# 21318.net
KiCad netlist of a schematic drawn in EAGLE
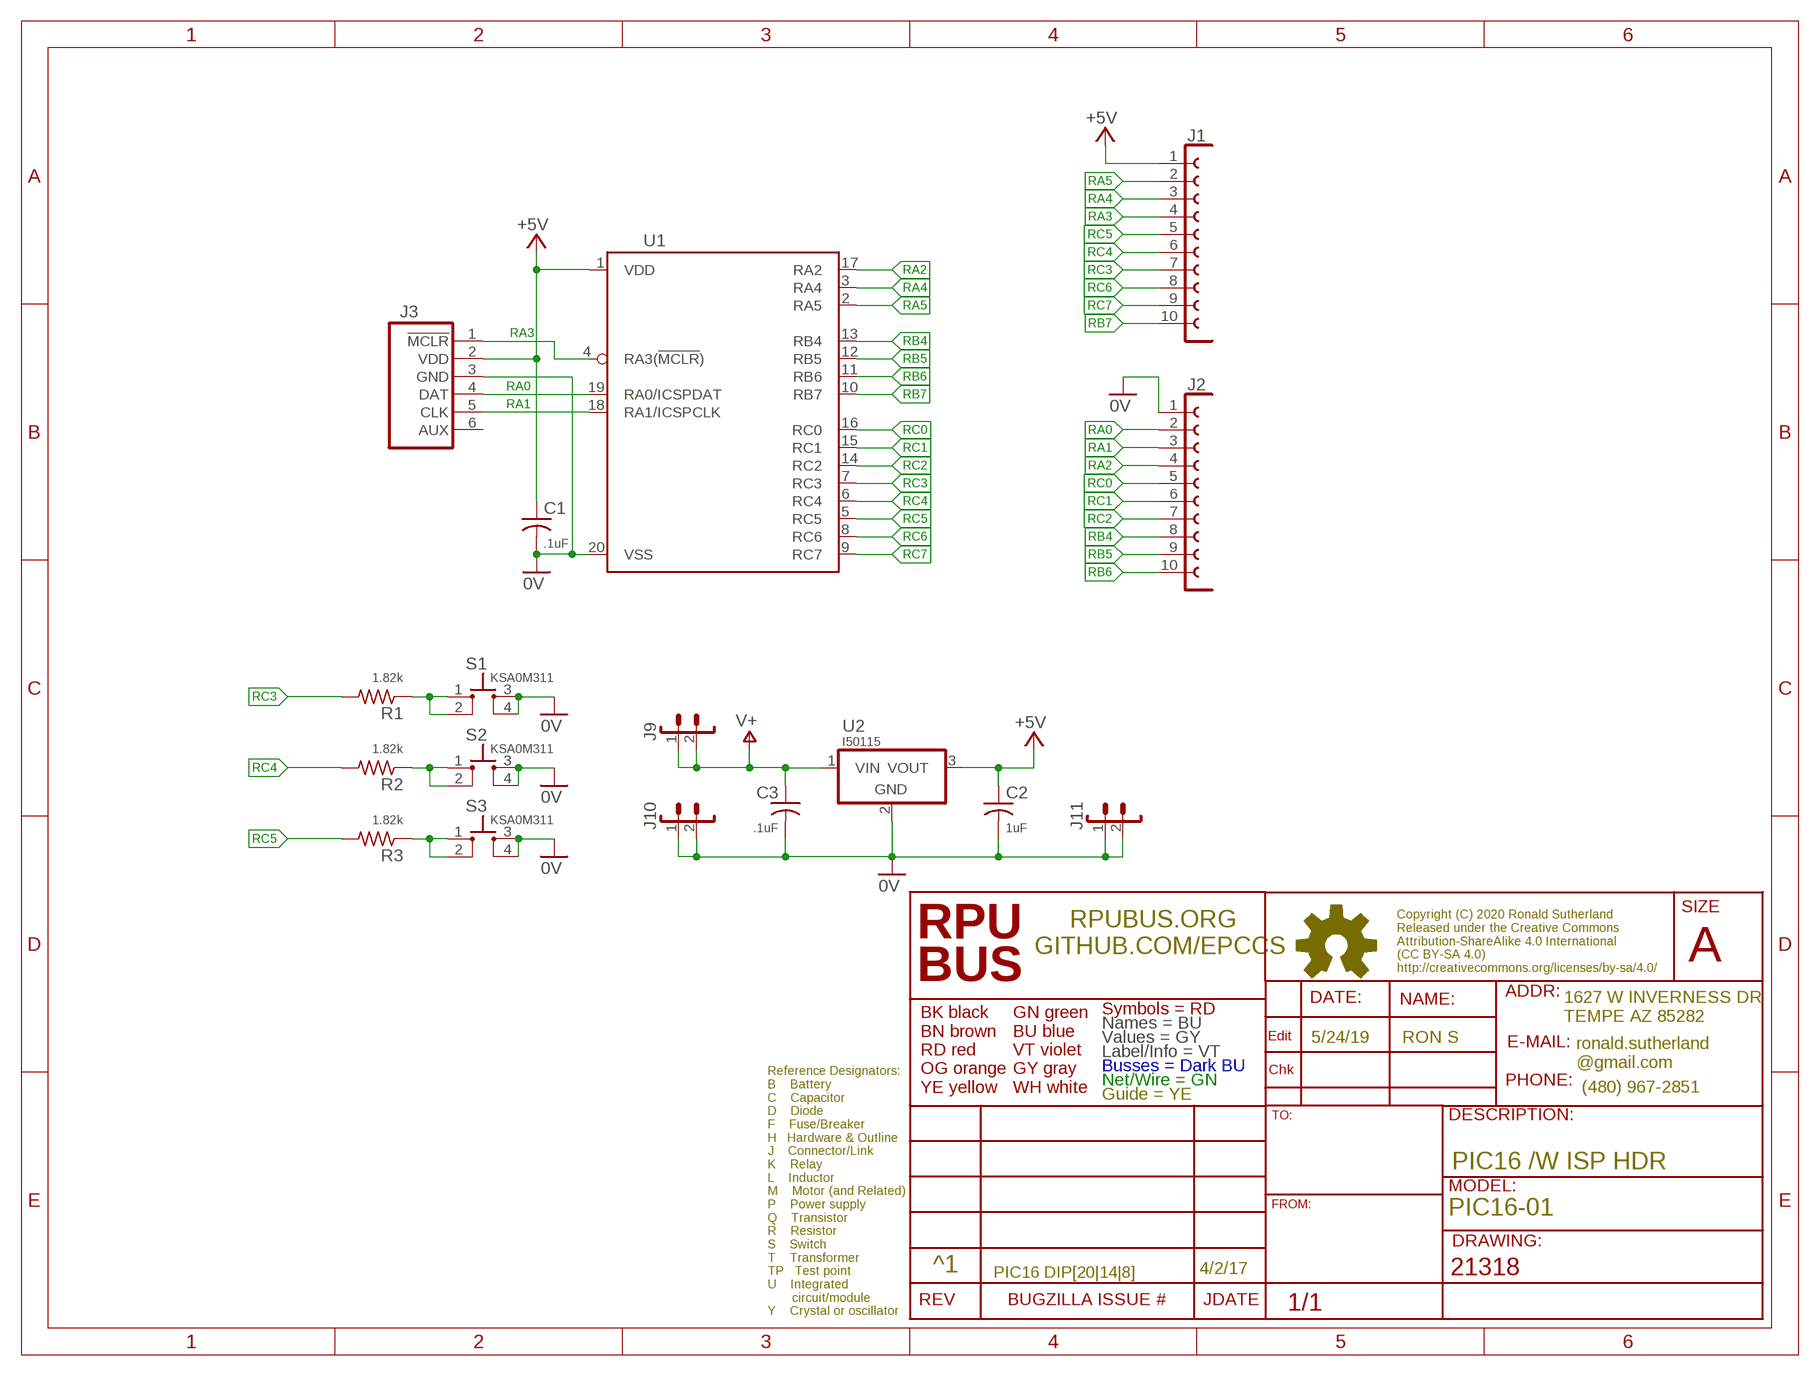
[diagram p0: schematic, sheet 1]

(export (version "E")
  (design (tool "Eeschema 10.0.6"))
  (components
    (comp (ref "C1")
      (value ".1uF")
      (footprint "eagle-import:C0603(1608)")
      (libsource (lib "eagle-import") (part "CC0603A"))
    )
    (comp (ref "C2")
      (value "1uF")
      (footprint "eagle-import:C0805(2012)")
      (libsource (lib "eagle-import") (part "CC0805A"))
    )
    (comp (ref "C3")
      (value ".1uF")
      (footprint "eagle-import:C0603(1608)")
      (libsource (lib "eagle-import") (part "CC0603A"))
    )
    (comp (ref "J1")
      (value "F1X10")
      (footprint "eagle-import:F1X10")
      (libsource (lib "eagle-import") (part "F1X10"))
    )
    (comp (ref "J2")
      (value "F1X10")
      (footprint "eagle-import:F1X10")
      (libsource (lib "eagle-import") (part "F1X10"))
    )
    (comp (ref "J3")
      (value "ISP")
      (footprint "eagle-import:ISP")
      (libsource (lib "eagle-import") (part "ISP"))
    )
    (comp (ref "J9")
      (value "1X2")
      (footprint "eagle-import:1X2")
      (libsource (lib "eagle-import") (part "1X2"))
    )
    (comp (ref "J10")
      (value "1X2")
      (footprint "eagle-import:1X2")
      (libsource (lib "eagle-import") (part "1X2"))
    )
    (comp (ref "J11")
      (value "1X2")
      (footprint "eagle-import:1X2")
      (libsource (lib "eagle-import") (part "1X2"))
    )
    (comp (ref "R1")
      (value "1.82k")
      (footprint "eagle-import:C0805(2012)")
      (libsource (lib "eagle-import") (part "R0805"))
    )
    (comp (ref "R2")
      (value "1.82k")
      (footprint "eagle-import:C0805(2012)")
      (libsource (lib "eagle-import") (part "R0805"))
    )
    (comp (ref "R3")
      (value "1.82k")
      (footprint "eagle-import:C0805(2012)")
      (libsource (lib "eagle-import") (part "R0805"))
    )
    (comp (ref "S1")
      (value "KSA0M311")
      (footprint "eagle-import:0M311")
      (libsource (lib "eagle-import") (part "KSA0M311"))
    )
    (comp (ref "S2")
      (value "KSA0M311")
      (footprint "eagle-import:0M311")
      (libsource (lib "eagle-import") (part "KSA0M311"))
    )
    (comp (ref "S3")
      (value "KSA0M311")
      (footprint "eagle-import:0M311")
      (libsource (lib "eagle-import") (part "KSA0M311"))
    )
    (comp (ref "U1")
      (value "PIC16F18346-I/P")
      (footprint "eagle-import:DIL20")
      (libsource (lib "eagle-import") (part "PIC16F18346-I/P"))
    )
    (comp (ref "U2")
      (value "I50115")
      (footprint "eagle-import:OKI-78SR-H")
      (libsource (lib "eagle-import") (part "OKI-78SR-H"))
    )
  )
  (nets
    (net (code "1") (name "+5V") (class "Default")
      (node (ref "C1") (pin "1") (pinfunction "1_1") (pintype "passive"))
      (node (ref "C2") (pin "1") (pinfunction "1_1") (pintype "passive"))
      (node (ref "J1") (pin "1") (pinfunction "1_1") (pintype "passive"))
      (node (ref "J3") (pin "2") (pinfunction "VDD_2") (pintype "bidirectional"))
      (node (ref "U1") (pin "1") (pinfunction "VDD_1") (pintype "power_in"))
      (node (ref "U2") (pin "3") (pinfunction "VOUT_3") (pintype "passive"))
    )
    (net (code "2") (name "0V") (class "Default")
      (node (ref "C1") (pin "2") (pinfunction "2_2") (pintype "passive"))
      (node (ref "C2") (pin "2") (pinfunction "2_2") (pintype "passive"))
      (node (ref "C3") (pin "2") (pinfunction "2_2") (pintype "passive"))
      (node (ref "J10") (pin "1") (pinfunction "1_1") (pintype "passive"))
      (node (ref "J10") (pin "2") (pinfunction "2_2") (pintype "passive"))
      (node (ref "J11") (pin "1") (pinfunction "1_1") (pintype "passive"))
      (node (ref "J11") (pin "2") (pinfunction "2_2") (pintype "passive"))
      (node (ref "J2") (pin "1") (pinfunction "1_1") (pintype "passive"))
      (node (ref "J3") (pin "3") (pinfunction "GND_3") (pintype "bidirectional"))
      (node (ref "S1") (pin "3") (pinfunction "3_3") (pintype "passive"))
      (node (ref "S1") (pin "4") (pinfunction "4_4") (pintype "passive"))
      (node (ref "S2") (pin "3") (pinfunction "3_3") (pintype "passive"))
      (node (ref "S2") (pin "4") (pinfunction "4_4") (pintype "passive"))
      (node (ref "S3") (pin "3") (pinfunction "3_3") (pintype "passive"))
      (node (ref "S3") (pin "4") (pinfunction "4_4") (pintype "passive"))
      (node (ref "U1") (pin "20") (pinfunction "VSS_20") (pintype "power_in"))
      (node (ref "U2") (pin "2") (pinfunction "GND_2") (pintype "passive"))
    )
    (net (code "3") (name "Net-(R1-Pad1)") (class "Default")
      (node (ref "R1") (pin "1") (pinfunction "1_1") (pintype "passive"))
      (node (ref "S1") (pin "1") (pinfunction "1_1") (pintype "passive"))
      (node (ref "S1") (pin "2") (pinfunction "2_2") (pintype "passive"))
    )
    (net (code "4") (name "Net-(R2-Pad1)") (class "Default")
      (node (ref "R2") (pin "1") (pinfunction "1_1") (pintype "passive"))
      (node (ref "S2") (pin "1") (pinfunction "1_1") (pintype "passive"))
      (node (ref "S2") (pin "2") (pinfunction "2_2") (pintype "passive"))
    )
    (net (code "5") (name "Net-(R3-Pad1)") (class "Default")
      (node (ref "R3") (pin "1") (pinfunction "1_1") (pintype "passive"))
      (node (ref "S3") (pin "1") (pinfunction "1_1") (pintype "passive"))
      (node (ref "S3") (pin "2") (pinfunction "2_2") (pintype "passive"))
    )
    (net (code "6") (name "RA0") (class "Default")
      (node (ref "J2") (pin "2") (pinfunction "2_2") (pintype "passive"))
      (node (ref "J3") (pin "4") (pinfunction "DAT_4") (pintype "bidirectional"))
      (node (ref "U1") (pin "19") (pinfunction "RA0/ICSPDAT_19") (pintype "bidirectional"))
    )
    (net (code "7") (name "RA1") (class "Default")
      (node (ref "J2") (pin "3") (pinfunction "3_3") (pintype "passive"))
      (node (ref "J3") (pin "5") (pinfunction "CLK_5") (pintype "bidirectional"))
      (node (ref "U1") (pin "18") (pinfunction "RA1/ICSPCLK_18") (pintype "bidirectional"))
    )
    (net (code "8") (name "RA2") (class "Default")
      (node (ref "J2") (pin "4") (pinfunction "4_4") (pintype "passive"))
      (node (ref "U1") (pin "17") (pinfunction "RA2_17") (pintype "bidirectional"))
    )
    (net (code "9") (name "RA3") (class "Default")
      (node (ref "J1") (pin "4") (pinfunction "4_4") (pintype "passive"))
      (node (ref "J3") (pin "1") (pinfunction "~{MCLR}_1") (pintype "bidirectional"))
      (node (ref "U1") (pin "4") (pinfunction "RA3(~{MCLR})_4") (pintype "bidirectional"))
    )
    (net (code "10") (name "RA4") (class "Default")
      (node (ref "J1") (pin "3") (pinfunction "3_3") (pintype "passive"))
      (node (ref "U1") (pin "3") (pinfunction "RA4_3") (pintype "bidirectional"))
    )
    (net (code "11") (name "RA5") (class "Default")
      (node (ref "J1") (pin "2") (pinfunction "2_2") (pintype "passive"))
      (node (ref "U1") (pin "2") (pinfunction "RA5_2") (pintype "bidirectional"))
    )
    (net (code "12") (name "RB4") (class "Default")
      (node (ref "J2") (pin "8") (pinfunction "8_8") (pintype "passive"))
      (node (ref "U1") (pin "13") (pinfunction "RB4_13") (pintype "bidirectional"))
    )
    (net (code "13") (name "RB5") (class "Default")
      (node (ref "J2") (pin "9") (pinfunction "9_9") (pintype "passive"))
      (node (ref "U1") (pin "12") (pinfunction "RB5_12") (pintype "bidirectional"))
    )
    (net (code "14") (name "RB6") (class "Default")
      (node (ref "J2") (pin "10") (pinfunction "10_10") (pintype "passive"))
      (node (ref "U1") (pin "11") (pinfunction "RB6_11") (pintype "bidirectional"))
    )
    (net (code "15") (name "RB7") (class "Default")
      (node (ref "J1") (pin "10") (pinfunction "10_10") (pintype "passive"))
      (node (ref "U1") (pin "10") (pinfunction "RB7_10") (pintype "bidirectional"))
    )
    (net (code "16") (name "RC0") (class "Default")
      (node (ref "J2") (pin "5") (pinfunction "5_5") (pintype "passive"))
      (node (ref "U1") (pin "16") (pinfunction "RC0_16") (pintype "bidirectional"))
    )
    (net (code "17") (name "RC1") (class "Default")
      (node (ref "J2") (pin "6") (pinfunction "6_6") (pintype "passive"))
      (node (ref "U1") (pin "15") (pinfunction "RC1_15") (pintype "bidirectional"))
    )
    (net (code "18") (name "RC2") (class "Default")
      (node (ref "J2") (pin "7") (pinfunction "7_7") (pintype "passive"))
      (node (ref "U1") (pin "14") (pinfunction "RC2_14") (pintype "bidirectional"))
    )
    (net (code "19") (name "RC3") (class "Default")
      (node (ref "J1") (pin "7") (pinfunction "7_7") (pintype "passive"))
      (node (ref "R1") (pin "2") (pinfunction "2_2") (pintype "passive"))
      (node (ref "U1") (pin "7") (pinfunction "RC3_7") (pintype "bidirectional"))
    )
    (net (code "20") (name "RC4") (class "Default")
      (node (ref "J1") (pin "6") (pinfunction "6_6") (pintype "passive"))
      (node (ref "R2") (pin "2") (pinfunction "2_2") (pintype "passive"))
      (node (ref "U1") (pin "6") (pinfunction "RC4_6") (pintype "bidirectional"))
    )
    (net (code "21") (name "RC5") (class "Default")
      (node (ref "J1") (pin "5") (pinfunction "5_5") (pintype "passive"))
      (node (ref "R3") (pin "2") (pinfunction "2_2") (pintype "passive"))
      (node (ref "U1") (pin "5") (pinfunction "RC5_5") (pintype "bidirectional"))
    )
    (net (code "22") (name "RC6") (class "Default")
      (node (ref "J1") (pin "8") (pinfunction "8_8") (pintype "passive"))
      (node (ref "U1") (pin "8") (pinfunction "RC6_8") (pintype "bidirectional"))
    )
    (net (code "23") (name "RC7") (class "Default")
      (node (ref "J1") (pin "9") (pinfunction "9_9") (pintype "passive"))
      (node (ref "U1") (pin "9") (pinfunction "RC7_9") (pintype "bidirectional"))
    )
    (net (code "24") (name "V+") (class "Default")
      (node (ref "C3") (pin "1") (pinfunction "1_1") (pintype "passive"))
      (node (ref "J9") (pin "1") (pinfunction "1_1") (pintype "passive"))
      (node (ref "J9") (pin "2") (pinfunction "2_2") (pintype "passive"))
      (node (ref "U2") (pin "1") (pinfunction "VIN_1") (pintype "passive"))
    )
    (net (code "25") (name "unconnected-(J3-AUX-Pad6)") (class "Default")
      (node (ref "J3") (pin "6") (pinfunction "AUX_6") (pintype "bidirectional"))
    )
  )
)
